# CAS.net
KiCad netlist of a schematic drawn in EAGLE
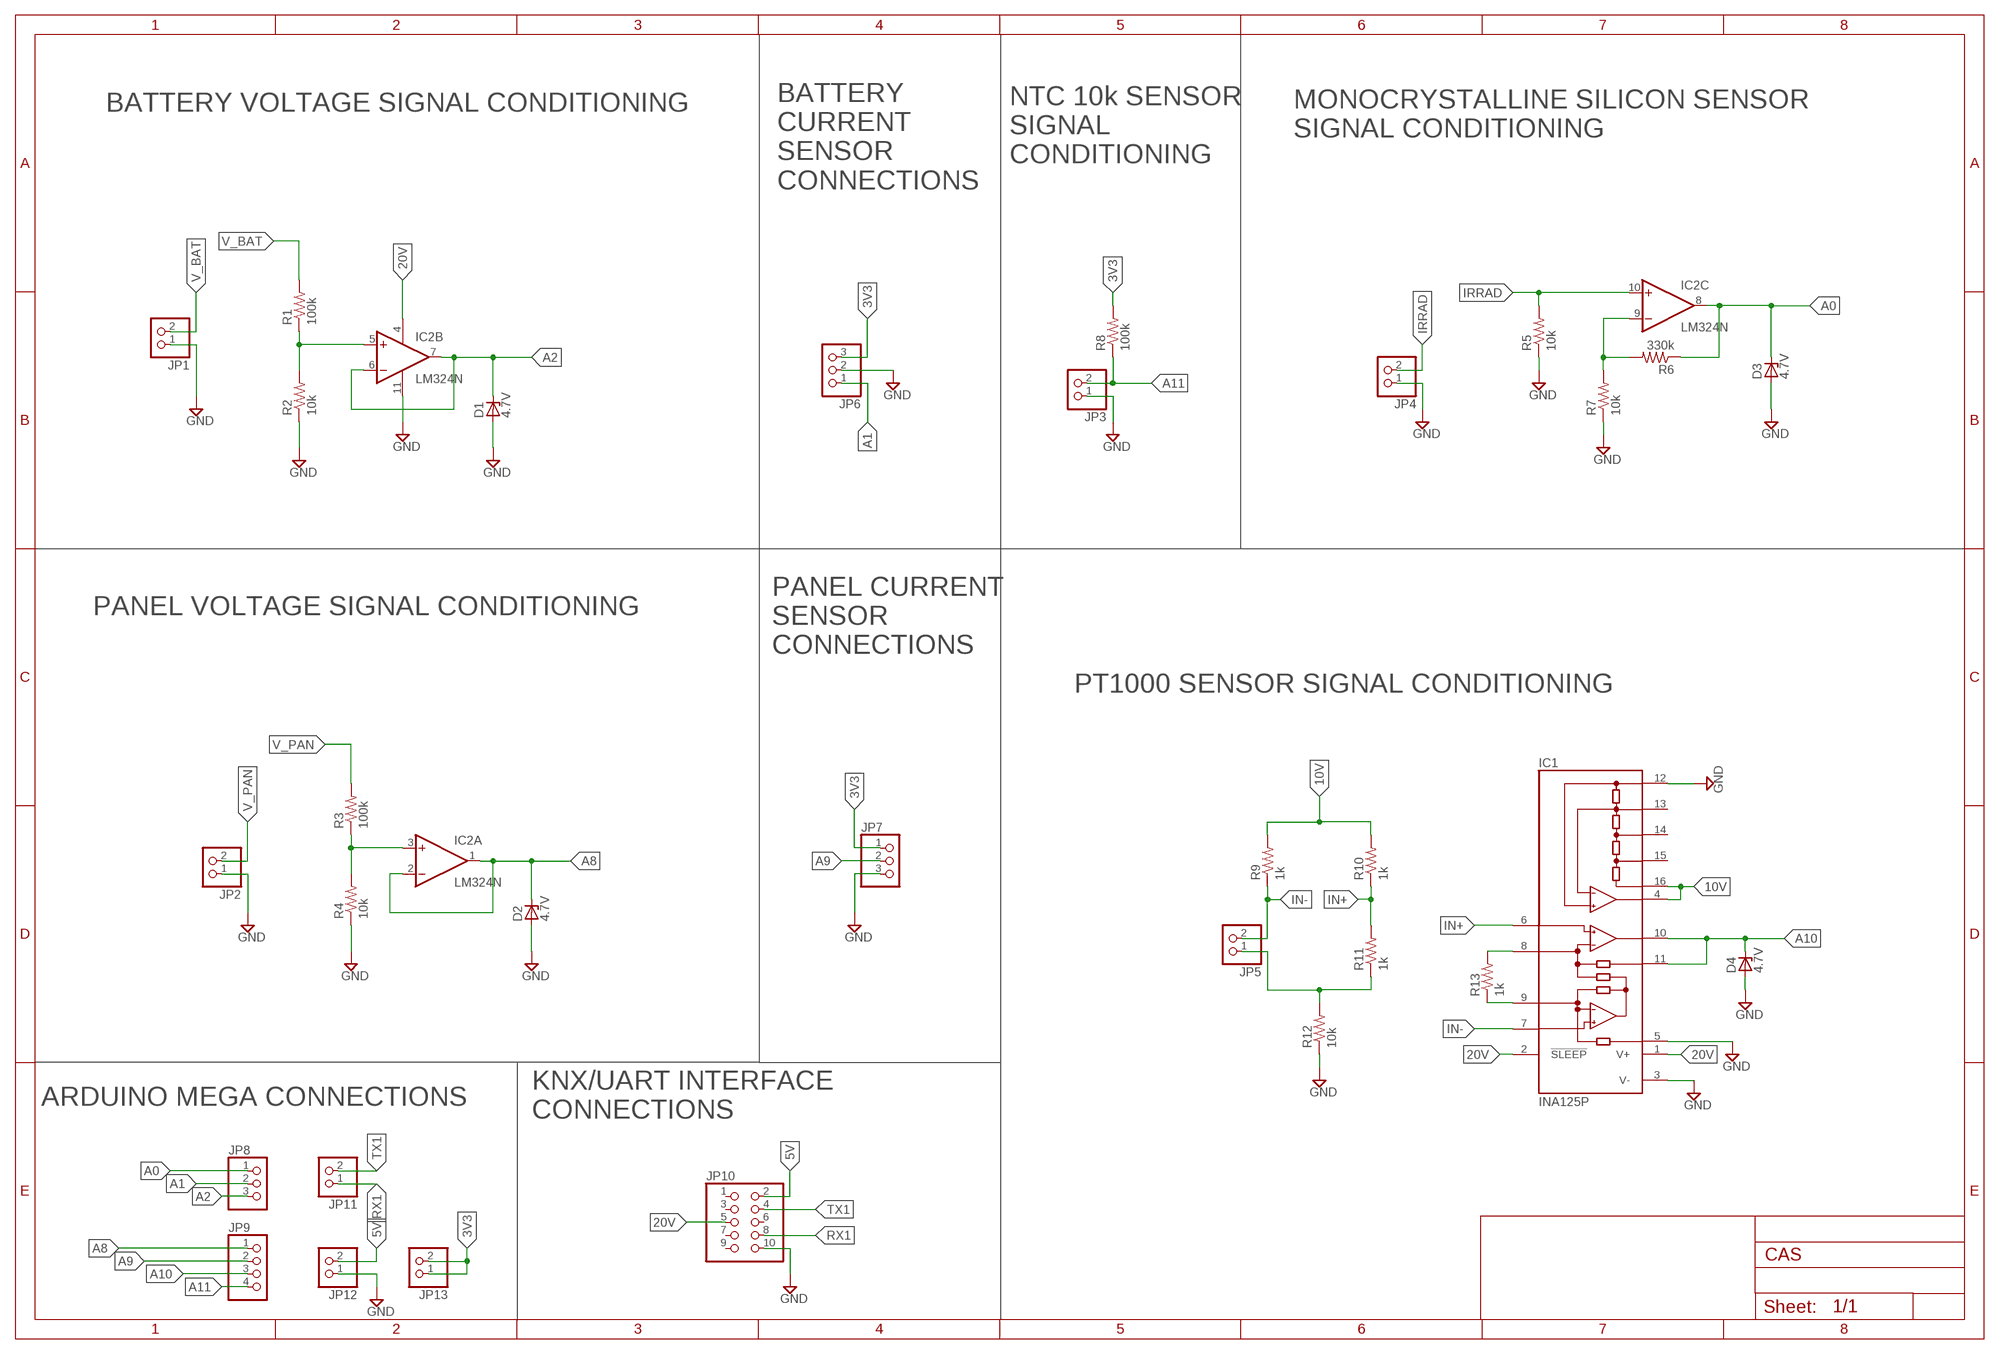
[diagram p0: schematic, sheet 1]

(export (version "E")
  (design (tool "Eeschema 10.0.6"))
  (components
    (comp (ref "D1")
      (value "4.7V")
      (footprint "eagle-import:DO41Z10")
      (libsource (lib "eagle-import") (part "ZENER-DIODEDO41Z10"))
    )
    (comp (ref "D2")
      (value "4.7V")
      (footprint "eagle-import:DO41Z10")
      (libsource (lib "eagle-import") (part "ZENER-DIODEDO41Z10"))
    )
    (comp (ref "D3")
      (value "4.7V")
      (footprint "eagle-import:DO41Z10")
      (libsource (lib "eagle-import") (part "ZENER-DIODEDO41Z10"))
    )
    (comp (ref "D4")
      (value "4.7V")
      (footprint "eagle-import:DO41Z10")
      (libsource (lib "eagle-import") (part "ZENER-DIODEDO41Z10"))
    )
    (comp (ref "IC1")
      (value "INA125P")
      (footprint "eagle-import:DIL16")
      (fields (field (name "MF") "TEXAS INSTRUMENT CONNECTORS"))
      (libsource (lib "eagle-import") (part "INA125P"))
    )
    (comp (ref "IC2")
      (value "LM324N")
      (footprint "eagle-import:DIL14")
      (libsource (lib "eagle-import") (part "LM324N"))
    )
    (comp (ref "JP1")
      (value "PINHD-1X2")
      (footprint "eagle-import:1X02")
      (libsource (lib "eagle-import") (part "PINHD-1X2"))
    )
    (comp (ref "JP2")
      (value "PINHD-1X2")
      (footprint "eagle-import:1X02")
      (libsource (lib "eagle-import") (part "PINHD-1X2"))
    )
    (comp (ref "JP3")
      (value "PINHD-1X2")
      (footprint "eagle-import:1X02")
      (libsource (lib "eagle-import") (part "PINHD-1X2"))
    )
    (comp (ref "JP4")
      (value "PINHD-1X2")
      (footprint "eagle-import:1X02")
      (libsource (lib "eagle-import") (part "PINHD-1X2"))
    )
    (comp (ref "JP5")
      (value "PINHD-1X2")
      (footprint "eagle-import:1X02")
      (libsource (lib "eagle-import") (part "PINHD-1X2"))
    )
    (comp (ref "JP6")
      (value "PINHD-1X3")
      (footprint "eagle-import:1X03")
      (libsource (lib "eagle-import") (part "PINHD-1X3"))
    )
    (comp (ref "JP7")
      (value "PINHD-1X3")
      (footprint "eagle-import:1X03")
      (libsource (lib "eagle-import") (part "PINHD-1X3"))
    )
    (comp (ref "JP8")
      (value "PINHD-1X3")
      (footprint "eagle-import:1X03")
      (libsource (lib "eagle-import") (part "PINHD-1X3"))
    )
    (comp (ref "JP9")
      (value "PINHD-1X4")
      (footprint "eagle-import:1X04")
      (libsource (lib "eagle-import") (part "PINHD-1X4"))
    )
    (comp (ref "JP10")
      (value "PINHD-2X5")
      (footprint "eagle-import:2X05")
      (libsource (lib "eagle-import") (part "PINHD-2X5"))
    )
    (comp (ref "JP11")
      (value "PINHD-1X2")
      (footprint "eagle-import:1X02")
      (libsource (lib "eagle-import") (part "PINHD-1X2"))
    )
    (comp (ref "JP12")
      (value "PINHD-1X2")
      (footprint "eagle-import:1X02")
      (libsource (lib "eagle-import") (part "PINHD-1X2"))
    )
    (comp (ref "JP13")
      (value "PINHD-1X2")
      (footprint "eagle-import:1X02")
      (libsource (lib "eagle-import") (part "PINHD-1X2"))
    )
    (comp (ref "R1")
      (value "100k")
      (footprint "eagle-import:0207_10")
      (libsource (lib "eagle-import") (part "R-US_0207/10"))
    )
    (comp (ref "R2")
      (value "10k")
      (footprint "eagle-import:0207_10")
      (libsource (lib "eagle-import") (part "R-US_0207/10"))
    )
    (comp (ref "R3")
      (value "100k")
      (footprint "eagle-import:0207_10")
      (libsource (lib "eagle-import") (part "R-US_0207/10"))
    )
    (comp (ref "R4")
      (value "10k")
      (footprint "eagle-import:0207_10")
      (libsource (lib "eagle-import") (part "R-US_0207/10"))
    )
    (comp (ref "R5")
      (value "10k")
      (footprint "eagle-import:0207_10")
      (libsource (lib "eagle-import") (part "R-US_0207/10"))
    )
    (comp (ref "R6")
      (value "330k")
      (footprint "eagle-import:0207_10")
      (libsource (lib "eagle-import") (part "R-US_0207/10"))
    )
    (comp (ref "R7")
      (value "10k")
      (footprint "eagle-import:0207_10")
      (libsource (lib "eagle-import") (part "R-US_0207/10"))
    )
    (comp (ref "R8")
      (value "100k")
      (footprint "eagle-import:0207_10")
      (libsource (lib "eagle-import") (part "R-US_0207/10"))
    )
    (comp (ref "R9")
      (value "1k")
      (footprint "eagle-import:0207_10")
      (libsource (lib "eagle-import") (part "R-US_0207/10"))
    )
    (comp (ref "R10")
      (value "1k")
      (footprint "eagle-import:0207_10")
      (libsource (lib "eagle-import") (part "R-US_0207/10"))
    )
    (comp (ref "R11")
      (value "1k")
      (footprint "eagle-import:0207_10")
      (libsource (lib "eagle-import") (part "R-US_0207/10"))
    )
    (comp (ref "R12")
      (value "10k")
      (footprint "eagle-import:0207_10")
      (libsource (lib "eagle-import") (part "R-US_0207/10"))
    )
    (comp (ref "R13")
      (value "1k")
      (footprint "eagle-import:0207_10")
      (libsource (lib "eagle-import") (part "R-US_0207/10"))
    )
  )
  (nets
    (net (code "1") (name "3V3") (class "Default")
      (node (ref "JP13") (pin "1") (pinfunction "1_1") (pintype "passive"))
      (node (ref "JP13") (pin "2") (pinfunction "2_2") (pintype "passive"))
      (node (ref "JP6") (pin "3") (pinfunction "3_3") (pintype "passive"))
      (node (ref "JP7") (pin "1") (pinfunction "1_1") (pintype "passive"))
      (node (ref "R8") (pin "2") (pinfunction "2_2") (pintype "passive"))
    )
    (net (code "2") (name "5V") (class "Default")
      (node (ref "JP10") (pin "2") (pinfunction "2_2") (pintype "passive"))
      (node (ref "JP12") (pin "2") (pinfunction "2_2") (pintype "passive"))
    )
    (net (code "3") (name "10V") (class "Default")
      (node (ref "IC1") (pin "16") (pinfunction "REF10_16") (pintype "output"))
      (node (ref "IC1") (pin "4") (pinfunction "REFOUT_4") (pintype "output"))
      (node (ref "R10") (pin "2") (pinfunction "2_2") (pintype "passive"))
      (node (ref "R9") (pin "2") (pinfunction "2_2") (pintype "passive"))
    )
    (net (code "4") (name "20V") (class "Default")
      (node (ref "IC1") (pin "1") (pinfunction "V+_1") (pintype "power_in"))
      (node (ref "IC1") (pin "2") (pinfunction "~{SLEEP}_2") (pintype "input"))
      (node (ref "IC2") (pin "4") (pinfunction "V+_4") (pintype "power_in"))
      (node (ref "JP10") (pin "5") (pinfunction "5_5") (pintype "passive"))
    )
    (net (code "5") (name "A0") (class "Default")
      (node (ref "D3") (pin "C") (pinfunction "C_C") (pintype "passive"))
      (node (ref "IC2") (pin "8") (pinfunction "OUT_8") (pintype "output"))
      (node (ref "JP8") (pin "1") (pinfunction "1_1") (pintype "passive"))
      (node (ref "R6") (pin "1") (pinfunction "1_1") (pintype "passive"))
    )
    (net (code "6") (name "A1") (class "Default")
      (node (ref "JP6") (pin "1") (pinfunction "1_1") (pintype "passive"))
      (node (ref "JP8") (pin "2") (pinfunction "2_2") (pintype "passive"))
    )
    (net (code "7") (name "A2") (class "Default")
      (node (ref "D1") (pin "C") (pinfunction "C_C") (pintype "passive"))
      (node (ref "IC2") (pin "6") (pinfunction "-IN_6") (pintype "input"))
      (node (ref "IC2") (pin "7") (pinfunction "OUT_7") (pintype "output"))
      (node (ref "JP8") (pin "3") (pinfunction "3_3") (pintype "passive"))
    )
    (net (code "8") (name "A8") (class "Default")
      (node (ref "D2") (pin "C") (pinfunction "C_C") (pintype "passive"))
      (node (ref "IC2") (pin "1") (pinfunction "OUT_1") (pintype "output"))
      (node (ref "IC2") (pin "2") (pinfunction "-IN_2") (pintype "input"))
      (node (ref "JP9") (pin "1") (pinfunction "1_1") (pintype "passive"))
    )
    (net (code "9") (name "A9") (class "Default")
      (node (ref "JP7") (pin "2") (pinfunction "2_2") (pintype "passive"))
      (node (ref "JP9") (pin "2") (pinfunction "2_2") (pintype "passive"))
    )
    (net (code "10") (name "A10") (class "Default")
      (node (ref "D4") (pin "C") (pinfunction "C_C") (pintype "passive"))
      (node (ref "IC1") (pin "10") (pinfunction "OUT_10") (pintype "output"))
      (node (ref "IC1") (pin "11") (pinfunction "SENSE_11") (pintype "passive"))
      (node (ref "JP9") (pin "3") (pinfunction "3_3") (pintype "passive"))
    )
    (net (code "11") (name "A11") (class "Default")
      (node (ref "JP3") (pin "2") (pinfunction "2_2") (pintype "passive"))
      (node (ref "JP9") (pin "4") (pinfunction "4_4") (pintype "passive"))
      (node (ref "R8") (pin "1") (pinfunction "1_1") (pintype "passive"))
    )
    (net (code "12") (name "GND") (class "Default")
      (node (ref "D1") (pin "A") (pinfunction "A_A") (pintype "passive"))
      (node (ref "D2") (pin "A") (pinfunction "A_A") (pintype "passive"))
      (node (ref "D3") (pin "A") (pinfunction "A_A") (pintype "passive"))
      (node (ref "D4") (pin "A") (pinfunction "A_A") (pintype "passive"))
      (node (ref "IC1") (pin "12") (pinfunction "REFCOM_12") (pintype "passive"))
      (node (ref "IC1") (pin "3") (pinfunction "V-_3") (pintype "power_in"))
      (node (ref "IC1") (pin "5") (pinfunction "REF_5") (pintype "passive"))
      (node (ref "IC2") (pin "11") (pinfunction "V-_11") (pintype "power_in"))
      (node (ref "JP1") (pin "1") (pinfunction "1_1") (pintype "passive"))
      (node (ref "JP10") (pin "10") (pinfunction "10_10") (pintype "passive"))
      (node (ref "JP12") (pin "1") (pinfunction "1_1") (pintype "passive"))
      (node (ref "JP2") (pin "1") (pinfunction "1_1") (pintype "passive"))
      (node (ref "JP3") (pin "1") (pinfunction "1_1") (pintype "passive"))
      (node (ref "JP4") (pin "1") (pinfunction "1_1") (pintype "passive"))
      (node (ref "JP6") (pin "2") (pinfunction "2_2") (pintype "passive"))
      (node (ref "JP7") (pin "3") (pinfunction "3_3") (pintype "passive"))
      (node (ref "R12") (pin "1") (pinfunction "1_1") (pintype "passive"))
      (node (ref "R2") (pin "1") (pinfunction "1_1") (pintype "passive"))
      (node (ref "R4") (pin "1") (pinfunction "1_1") (pintype "passive"))
      (node (ref "R5") (pin "1") (pinfunction "1_1") (pintype "passive"))
      (node (ref "R7") (pin "1") (pinfunction "1_1") (pintype "passive"))
    )
    (net (code "13") (name "IN+") (class "Default")
      (node (ref "IC1") (pin "6") (pinfunction "+IN_6") (pintype "input"))
      (node (ref "R10") (pin "1") (pinfunction "1_1") (pintype "passive"))
      (node (ref "R11") (pin "2") (pinfunction "2_2") (pintype "passive"))
    )
    (net (code "14") (name "IN-") (class "Default")
      (node (ref "IC1") (pin "7") (pinfunction "-IN_7") (pintype "input"))
      (node (ref "JP5") (pin "2") (pinfunction "2_2") (pintype "passive"))
      (node (ref "R9") (pin "1") (pinfunction "1_1") (pintype "passive"))
    )
    (net (code "15") (name "IRRAD") (class "Default")
      (node (ref "IC2") (pin "10") (pinfunction "+IN_10") (pintype "input"))
      (node (ref "JP4") (pin "2") (pinfunction "2_2") (pintype "passive"))
      (node (ref "R5") (pin "2") (pinfunction "2_2") (pintype "passive"))
    )
    (net (code "16") (name "Net-(IC1-RG-Pad8)") (class "Default")
      (node (ref "IC1") (pin "8") (pinfunction "RG_8") (pintype "passive"))
      (node (ref "R13") (pin "2") (pinfunction "2_2") (pintype "passive"))
    )
    (net (code "17") (name "Net-(IC1-RG-Pad9)") (class "Default")
      (node (ref "IC1") (pin "9") (pinfunction "RG_9") (pintype "passive"))
      (node (ref "R13") (pin "1") (pinfunction "1_1") (pintype "passive"))
    )
    (net (code "18") (name "Net-(IC2A-+IN)") (class "Default")
      (node (ref "IC2") (pin "3") (pinfunction "+IN_3") (pintype "input"))
      (node (ref "R3") (pin "1") (pinfunction "1_1") (pintype "passive"))
      (node (ref "R4") (pin "2") (pinfunction "2_2") (pintype "passive"))
    )
    (net (code "19") (name "Net-(IC2B-+IN)") (class "Default")
      (node (ref "IC2") (pin "5") (pinfunction "+IN_5") (pintype "input"))
      (node (ref "R1") (pin "1") (pinfunction "1_1") (pintype "passive"))
      (node (ref "R2") (pin "2") (pinfunction "2_2") (pintype "passive"))
    )
    (net (code "20") (name "Net-(IC2C--IN)") (class "Default")
      (node (ref "IC2") (pin "9") (pinfunction "-IN_9") (pintype "input"))
      (node (ref "R6") (pin "2") (pinfunction "2_2") (pintype "passive"))
      (node (ref "R7") (pin "2") (pinfunction "2_2") (pintype "passive"))
    )
    (net (code "21") (name "Net-(JP5-Pad1)") (class "Default")
      (node (ref "JP5") (pin "1") (pinfunction "1_1") (pintype "passive"))
      (node (ref "R11") (pin "1") (pinfunction "1_1") (pintype "passive"))
      (node (ref "R12") (pin "2") (pinfunction "2_2") (pintype "passive"))
    )
    (net (code "22") (name "RX1") (class "Default")
      (node (ref "JP10") (pin "8") (pinfunction "8_8") (pintype "passive"))
      (node (ref "JP11") (pin "1") (pinfunction "1_1") (pintype "passive"))
    )
    (net (code "23") (name "TX1") (class "Default")
      (node (ref "JP10") (pin "4") (pinfunction "4_4") (pintype "passive"))
      (node (ref "JP11") (pin "2") (pinfunction "2_2") (pintype "passive"))
    )
    (net (code "24") (name "V_BAT") (class "Default")
      (node (ref "JP1") (pin "2") (pinfunction "2_2") (pintype "passive"))
      (node (ref "R1") (pin "2") (pinfunction "2_2") (pintype "passive"))
    )
    (net (code "25") (name "V_PAN") (class "Default")
      (node (ref "JP2") (pin "2") (pinfunction "2_2") (pintype "passive"))
      (node (ref "R3") (pin "2") (pinfunction "2_2") (pintype "passive"))
    )
    (net (code "26") (name "unconnected-(IC1-REF2.5-Pad14)") (class "Default")
      (node (ref "IC1") (pin "14") (pinfunction "REF2.5_14") (pintype "output"))
    )
    (net (code "27") (name "unconnected-(IC1-REF5-Pad15)") (class "Default")
      (node (ref "IC1") (pin "15") (pinfunction "REF5_15") (pintype "output"))
    )
    (net (code "28") (name "unconnected-(IC1-REFBG-Pad13)") (class "Default")
      (node (ref "IC1") (pin "13") (pinfunction "REFBG_13") (pintype "output"))
    )
    (net (code "29") (name "unconnected-(JP10-Pad1)") (class "Default")
      (node (ref "JP10") (pin "1") (pinfunction "1_1") (pintype "passive"))
    )
    (net (code "30") (name "unconnected-(JP10-Pad3)") (class "Default")
      (node (ref "JP10") (pin "3") (pinfunction "3_3") (pintype "passive"))
    )
    (net (code "31") (name "unconnected-(JP10-Pad6)") (class "Default")
      (node (ref "JP10") (pin "6") (pinfunction "6_6") (pintype "passive"))
    )
    (net (code "32") (name "unconnected-(JP10-Pad7)") (class "Default")
      (node (ref "JP10") (pin "7") (pinfunction "7_7") (pintype "passive"))
    )
    (net (code "33") (name "unconnected-(JP10-Pad9)") (class "Default")
      (node (ref "JP10") (pin "9") (pinfunction "9_9") (pintype "passive"))
    )
  )
)
